# AccessBadgeV1_0.net
KiCad netlist of a schematic drawn in EAGLE
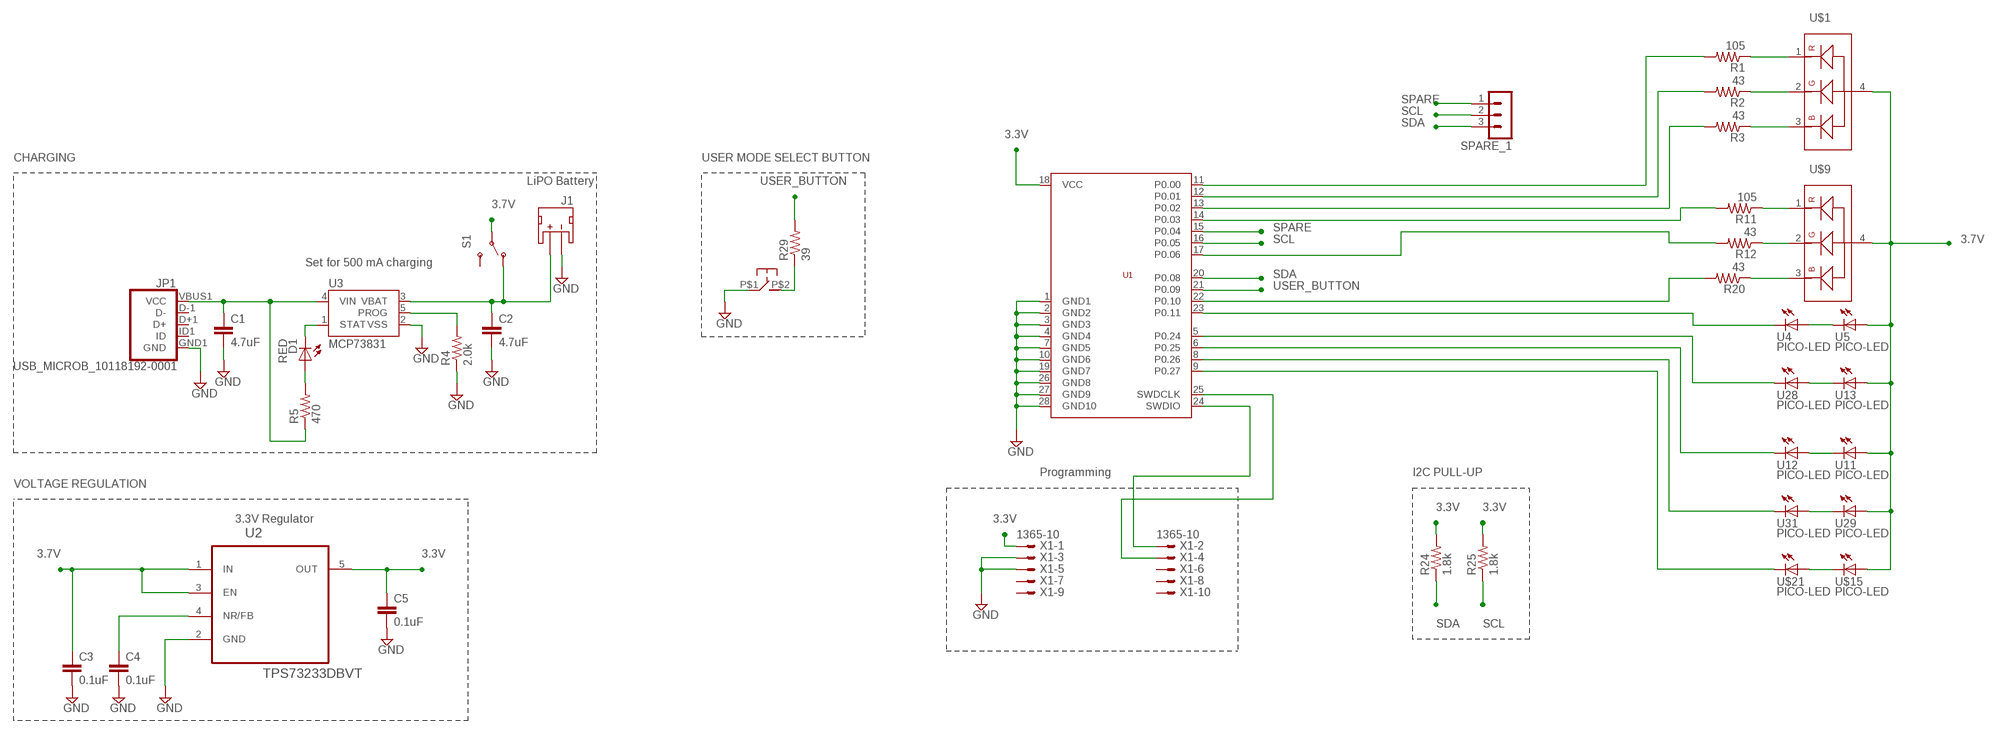
[diagram p0: schematic, sheet 1]

(export (version "E")
  (design (tool "Eeschema 10.0.6"))
  (components
    (comp (ref "C1")
      (value "4.7uF")
      (footprint "eagle-import:0603-CAP")
      (libsource (lib "eagle-import") (part "CAP0603-CAP"))
    )
    (comp (ref "C2")
      (value "4.7uF")
      (footprint "eagle-import:0603-CAP")
      (libsource (lib "eagle-import") (part "CAP0603-CAP"))
    )
    (comp (ref "C3")
      (value "0.1uF")
      (footprint "eagle-import:C0201")
      (libsource (lib "eagle-import") (part "C-EUC0201"))
    )
    (comp (ref "C4")
      (value "0.1uF")
      (footprint "eagle-import:C0201")
      (libsource (lib "eagle-import") (part "C-EUC0201"))
    )
    (comp (ref "C5")
      (value "0.1uF")
      (footprint "eagle-import:C0201")
      (libsource (lib "eagle-import") (part "C-EUC0201"))
    )
    (comp (ref "D1")
      (value "RED")
      (footprint "eagle-import:CHIP-LED0603")
      (libsource (lib "eagle-import") (part "LEDCHIP-LED0603"))
    )
    (comp (ref "J1")
      (value "JST_2MM_MALE")
      (footprint "eagle-import:JST-2-SMD")
      (libsource (lib "eagle-import") (part "JST_2MM_MALE"))
    )
    (comp (ref "JP1")
      (value "USB_MICROB_10118192-0001")
      (footprint "eagle-import:USB-B-MICRO-SMD_V03")
      (libsource (lib "eagle-import") (part "USB_MICROB_PLUGCONN-11752"))
    )
    (comp (ref "R1")
      (value "105")
      (footprint "eagle-import:R0201")
      (libsource (lib "eagle-import") (part "R-US_R0201"))
    )
    (comp (ref "R2")
      (value "43")
      (footprint "eagle-import:R0201")
      (libsource (lib "eagle-import") (part "R-US_R0201"))
    )
    (comp (ref "R3")
      (value "43")
      (footprint "eagle-import:R0201")
      (libsource (lib "eagle-import") (part "R-US_R0201"))
    )
    (comp (ref "R4")
      (value "2.0k")
      (footprint "eagle-import:R0201")
      (libsource (lib "eagle-import") (part "R-US_R0201"))
    )
    (comp (ref "R5")
      (value "470")
      (footprint "eagle-import:R0201")
      (libsource (lib "eagle-import") (part "R-US_R0201"))
    )
    (comp (ref "R11")
      (value "105")
      (footprint "eagle-import:R0201")
      (libsource (lib "eagle-import") (part "R-US_R0201"))
    )
    (comp (ref "R12")
      (value "43")
      (footprint "eagle-import:R0201")
      (libsource (lib "eagle-import") (part "R-US_R0201"))
    )
    (comp (ref "R20")
      (value "43")
      (footprint "eagle-import:R0201")
      (libsource (lib "eagle-import") (part "R-US_R0201"))
    )
    (comp (ref "R24")
      (value "1.8k")
      (footprint "eagle-import:R0201")
      (libsource (lib "eagle-import") (part "R-US_R0201"))
    )
    (comp (ref "R25")
      (value "1.8k")
      (footprint "eagle-import:R0201")
      (libsource (lib "eagle-import") (part "R-US_R0201"))
    )
    (comp (ref "R29")
      (value "39")
      (footprint "eagle-import:R0201")
      (libsource (lib "eagle-import") (part "R-US_R0201"))
    )
    (comp (ref "S1")
      (value "SWITCH-SPDTSMD2")
      (footprint "eagle-import:SWITCH-SPDT-SMD")
      (libsource (lib "eagle-import") (part "SWITCH-SPDTSMD2"))
    )
    (comp (ref "SLC")
      (value "TACTILE_BUTTON")
      (footprint "eagle-import:KXT131")
      (libsource (lib "eagle-import") (part "TACTILE_BUTTON"))
    )
    (comp (ref "SPARE_1")
      (value "MA03-1")
      (footprint "eagle-import:MA03-1")
      (libsource (lib "eagle-import") (part "MA03-1"))
    )
    (comp (ref "U$1")
      (value "RGB")
      (footprint "eagle-import:0606")
      (libsource (lib "eagle-import") (part "RGB"))
    )
    (comp (ref "U$9")
      (value "RGB")
      (footprint "eagle-import:0606")
      (libsource (lib "eagle-import") (part "RGB"))
    )
    (comp (ref "U$15")
      (value "PICO-LED")
      (footprint "eagle-import:CHIP-LED0402")
      (libsource (lib "eagle-import") (part "PICO-LED"))
    )
    (comp (ref "U$21")
      (value "PICO-LED")
      (footprint "eagle-import:CHIP-LED0402")
      (libsource (lib "eagle-import") (part "PICO-LED"))
    )
    (comp (ref "U1")
      (value "BMD-200")
      (footprint "eagle-import:BMD-200")
      (libsource (lib "eagle-import") (part "BMD-200"))
    )
    (comp (ref "U2")
      (value "TPS73233DBVT")
      (footprint "eagle-import:SOT95P280X145-5N")
      (libsource (lib "eagle-import") (part "TPS73233DBVT"))
    )
    (comp (ref "U3")
      (value "MCP73831")
      (footprint "eagle-import:SOT23-5")
      (libsource (lib "eagle-import") (part "MCP73831"))
    )
    (comp (ref "U4")
      (value "PICO-LED")
      (footprint "eagle-import:CHIP-LED0402")
      (libsource (lib "eagle-import") (part "PICO-LED"))
    )
    (comp (ref "U5")
      (value "PICO-LED")
      (footprint "eagle-import:CHIP-LED0402")
      (libsource (lib "eagle-import") (part "PICO-LED"))
    )
    (comp (ref "U11")
      (value "PICO-LED")
      (footprint "eagle-import:CHIP-LED0402")
      (libsource (lib "eagle-import") (part "PICO-LED"))
    )
    (comp (ref "U12")
      (value "PICO-LED")
      (footprint "eagle-import:CHIP-LED0402")
      (libsource (lib "eagle-import") (part "PICO-LED"))
    )
    (comp (ref "U13")
      (value "PICO-LED")
      (footprint "eagle-import:CHIP-LED0402")
      (libsource (lib "eagle-import") (part "PICO-LED"))
    )
    (comp (ref "U28")
      (value "PICO-LED")
      (footprint "eagle-import:CHIP-LED0402")
      (libsource (lib "eagle-import") (part "PICO-LED"))
    )
    (comp (ref "U29")
      (value "PICO-LED")
      (footprint "eagle-import:CHIP-LED0402")
      (libsource (lib "eagle-import") (part "PICO-LED"))
    )
    (comp (ref "U31")
      (value "PICO-LED")
      (footprint "eagle-import:CHIP-LED0402")
      (libsource (lib "eagle-import") (part "PICO-LED"))
    )
    (comp (ref "X1")
      (value "1365-10")
      (footprint "eagle-import:1365-10")
      (libsource (lib "eagle-import") (part "1365-10"))
    )
  )
  (nets
    (net (code "1") (name "/3.3V") (class "Default")
      (node (ref "C5") (pin "1") (pinfunction "1_1") (pintype "passive"))
      (node (ref "R24") (pin "2") (pinfunction "2_2") (pintype "passive"))
      (node (ref "R25") (pin "2") (pinfunction "2_2") (pintype "passive"))
      (node (ref "U1") (pin "18") (pinfunction "VCC_18") (pintype "bidirectional"))
      (node (ref "U2") (pin "5") (pinfunction "OUT_5") (pintype "output"))
      (node (ref "X1") (pin "1") (pinfunction "S_1") (pintype "passive"))
    )
    (net (code "2") (name "/3.7V") (class "Default")
      (node (ref "C3") (pin "1") (pinfunction "1_1") (pintype "passive"))
      (node (ref "S1") (pin "2") (pinfunction "P_2") (pintype "passive"))
      (node (ref "U$1") (pin "4") (pinfunction "4_4") (pintype "bidirectional"))
      (node (ref "U$15") (pin "P$1") (pinfunction "A_P$1") (pintype "passive"))
      (node (ref "U$9") (pin "4") (pinfunction "4_4") (pintype "bidirectional"))
      (node (ref "U11") (pin "P$1") (pinfunction "A_P$1") (pintype "passive"))
      (node (ref "U13") (pin "P$1") (pinfunction "A_P$1") (pintype "passive"))
      (node (ref "U2") (pin "1") (pinfunction "IN_1") (pintype "power_in"))
      (node (ref "U2") (pin "3") (pinfunction "EN_3") (pintype "input"))
      (node (ref "U29") (pin "P$1") (pinfunction "A_P$1") (pintype "passive"))
      (node (ref "U5") (pin "P$1") (pinfunction "A_P$1") (pintype "passive"))
    )
    (net (code "3") (name "/SCL") (class "Default")
      (node (ref "R25") (pin "1") (pinfunction "1_1") (pintype "passive"))
      (node (ref "SPARE_1") (pin "2") (pinfunction "2_2") (pintype "passive"))
      (node (ref "U1") (pin "16") (pinfunction "P0.05_16") (pintype "bidirectional"))
    )
    (net (code "4") (name "/SDA") (class "Default")
      (node (ref "R24") (pin "1") (pinfunction "1_1") (pintype "passive"))
      (node (ref "SPARE_1") (pin "3") (pinfunction "3_3") (pintype "passive"))
      (node (ref "U1") (pin "20") (pinfunction "P0.08_20") (pintype "bidirectional"))
    )
    (net (code "5") (name "/SPARE") (class "Default")
      (node (ref "SPARE_1") (pin "1") (pinfunction "1_1") (pintype "passive"))
      (node (ref "U1") (pin "15") (pinfunction "P0.04_15") (pintype "bidirectional"))
    )
    (net (code "6") (name "/USER_BUTTON") (class "Default")
      (node (ref "R29") (pin "2") (pinfunction "2_2") (pintype "passive"))
      (node (ref "U1") (pin "21") (pinfunction "P0.09_21") (pintype "bidirectional"))
    )
    (net (code "7") (name "GND") (class "Default")
      (node (ref "C1") (pin "2") (pinfunction "2_2") (pintype "passive"))
      (node (ref "C2") (pin "2") (pinfunction "2_2") (pintype "passive"))
      (node (ref "C3") (pin "2") (pinfunction "2_2") (pintype "passive"))
      (node (ref "C4") (pin "2") (pinfunction "2_2") (pintype "passive"))
      (node (ref "C5") (pin "2") (pinfunction "2_2") (pintype "passive"))
      (node (ref "J1") (pin "1") (pinfunction "-_1") (pintype "bidirectional"))
      (node (ref "JP1") (pin "GND1") (pinfunction "GND_GND1") (pintype "bidirectional"))
      (node (ref "R4") (pin "1") (pinfunction "1_1") (pintype "passive"))
      (node (ref "SLC") (pin "P$1") (pinfunction "P$1_P$1") (pintype "bidirectional"))
      (node (ref "U1") (pin "1") (pinfunction "GND1_1") (pintype "bidirectional"))
      (node (ref "U1") (pin "10") (pinfunction "GND6_10") (pintype "bidirectional"))
      (node (ref "U1") (pin "19") (pinfunction "GND7_19") (pintype "bidirectional"))
      (node (ref "U1") (pin "2") (pinfunction "GND2_2") (pintype "bidirectional"))
      (node (ref "U1") (pin "26") (pinfunction "GND8_26") (pintype "bidirectional"))
      (node (ref "U1") (pin "27") (pinfunction "GND9_27") (pintype "bidirectional"))
      (node (ref "U1") (pin "28") (pinfunction "GND10_28") (pintype "bidirectional"))
      (node (ref "U1") (pin "3") (pinfunction "GND3_3") (pintype "bidirectional"))
      (node (ref "U1") (pin "4") (pinfunction "GND4_4") (pintype "bidirectional"))
      (node (ref "U1") (pin "7") (pinfunction "GND5_7") (pintype "bidirectional"))
      (node (ref "U2") (pin "2") (pinfunction "GND_2") (pintype "passive"))
      (node (ref "U3") (pin "2") (pinfunction "VSS_2") (pintype "power_in"))
      (node (ref "X1") (pin "3") (pinfunction "S_3") (pintype "passive"))
      (node (ref "X1") (pin "5") (pinfunction "S_5") (pintype "passive"))
    )
    (net (code "8") (name "Net-(D1-PadA)") (class "Default")
      (node (ref "D1") (pin "A") (pinfunction "A_A") (pintype "passive"))
      (node (ref "R5") (pin "2") (pinfunction "2_2") (pintype "passive"))
    )
    (net (code "9") (name "Net-(J1-+)") (class "Default")
      (node (ref "C2") (pin "1") (pinfunction "1_1") (pintype "passive"))
      (node (ref "J1") (pin "2") (pinfunction "+_2") (pintype "bidirectional"))
      (node (ref "S1") (pin "1") (pinfunction "O_1") (pintype "passive"))
      (node (ref "U3") (pin "3") (pinfunction "VBAT_3") (pintype "power_in"))
    )
    (net (code "10") (name "Net-(JP1-VCC)") (class "Default")
      (node (ref "C1") (pin "1") (pinfunction "1_1") (pintype "passive"))
      (node (ref "JP1") (pin "VBUS1") (pinfunction "VCC_VBUS1") (pintype "bidirectional"))
      (node (ref "R5") (pin "1") (pinfunction "1_1") (pintype "passive"))
      (node (ref "U3") (pin "4") (pinfunction "VIN_4") (pintype "power_in"))
    )
    (net (code "11") (name "Net-(R1-Pad1)") (class "Default")
      (node (ref "R1") (pin "1") (pinfunction "1_1") (pintype "passive"))
      (node (ref "U$1") (pin "1") (pinfunction "1_1") (pintype "bidirectional"))
    )
    (net (code "12") (name "Net-(R2-Pad1)") (class "Default")
      (node (ref "R2") (pin "1") (pinfunction "1_1") (pintype "passive"))
      (node (ref "U$1") (pin "2") (pinfunction "2_2") (pintype "bidirectional"))
    )
    (net (code "13") (name "Net-(R3-Pad1)") (class "Default")
      (node (ref "R3") (pin "1") (pinfunction "1_1") (pintype "passive"))
      (node (ref "U$1") (pin "3") (pinfunction "3_3") (pintype "bidirectional"))
    )
    (net (code "14") (name "Net-(R11-Pad1)") (class "Default")
      (node (ref "R11") (pin "1") (pinfunction "1_1") (pintype "passive"))
      (node (ref "U$9") (pin "1") (pinfunction "1_1") (pintype "bidirectional"))
    )
    (net (code "15") (name "Net-(R12-Pad1)") (class "Default")
      (node (ref "R12") (pin "1") (pinfunction "1_1") (pintype "passive"))
      (node (ref "U$9") (pin "2") (pinfunction "2_2") (pintype "bidirectional"))
    )
    (net (code "16") (name "Net-(R20-Pad1)") (class "Default")
      (node (ref "R20") (pin "1") (pinfunction "1_1") (pintype "passive"))
      (node (ref "U$9") (pin "3") (pinfunction "3_3") (pintype "bidirectional"))
    )
    (net (code "17") (name "Net-(R29-Pad1)") (class "Default")
      (node (ref "R29") (pin "1") (pinfunction "1_1") (pintype "passive"))
      (node (ref "SLC") (pin "P$2") (pinfunction "P$2_P$2") (pintype "bidirectional"))
    )
    (net (code "18") (name "Net-(U$15-C)") (class "Default")
      (node (ref "U$15") (pin "P$2") (pinfunction "C_P$2") (pintype "passive"))
      (node (ref "U$21") (pin "P$1") (pinfunction "A_P$1") (pintype "passive"))
    )
    (net (code "19") (name "Net-(U$21-C)") (class "Default")
      (node (ref "U$21") (pin "P$2") (pinfunction "C_P$2") (pintype "passive"))
      (node (ref "U1") (pin "9") (pinfunction "P0.27_9") (pintype "bidirectional"))
    )
    (net (code "20") (name "Net-(U1-P0.00)") (class "Default")
      (node (ref "R1") (pin "2") (pinfunction "2_2") (pintype "passive"))
      (node (ref "U1") (pin "11") (pinfunction "P0.00_11") (pintype "bidirectional"))
    )
    (net (code "21") (name "Net-(U1-P0.01)") (class "Default")
      (node (ref "R2") (pin "2") (pinfunction "2_2") (pintype "passive"))
      (node (ref "U1") (pin "12") (pinfunction "P0.01_12") (pintype "bidirectional"))
    )
    (net (code "22") (name "Net-(U1-P0.02)") (class "Default")
      (node (ref "R3") (pin "2") (pinfunction "2_2") (pintype "passive"))
      (node (ref "U1") (pin "13") (pinfunction "P0.02_13") (pintype "bidirectional"))
    )
    (net (code "23") (name "Net-(U1-P0.03)") (class "Default")
      (node (ref "R11") (pin "2") (pinfunction "2_2") (pintype "passive"))
      (node (ref "U1") (pin "14") (pinfunction "P0.03_14") (pintype "bidirectional"))
    )
    (net (code "24") (name "Net-(U1-P0.06)") (class "Default")
      (node (ref "R12") (pin "2") (pinfunction "2_2") (pintype "passive"))
      (node (ref "U1") (pin "17") (pinfunction "P0.06_17") (pintype "bidirectional"))
    )
    (net (code "25") (name "Net-(U1-P0.10)") (class "Default")
      (node (ref "R20") (pin "2") (pinfunction "2_2") (pintype "passive"))
      (node (ref "U1") (pin "22") (pinfunction "P0.10_22") (pintype "bidirectional"))
    )
    (net (code "26") (name "Net-(U1-P0.11)") (class "Default")
      (node (ref "U1") (pin "23") (pinfunction "P0.11_23") (pintype "bidirectional"))
      (node (ref "U4") (pin "P$2") (pinfunction "C_P$2") (pintype "passive"))
    )
    (net (code "27") (name "Net-(U1-P0.24)") (class "Default")
      (node (ref "U1") (pin "5") (pinfunction "P0.24_5") (pintype "bidirectional"))
      (node (ref "U28") (pin "P$2") (pinfunction "C_P$2") (pintype "passive"))
    )
    (net (code "28") (name "Net-(U1-P0.25)") (class "Default")
      (node (ref "U1") (pin "6") (pinfunction "P0.25_6") (pintype "bidirectional"))
      (node (ref "U12") (pin "P$2") (pinfunction "C_P$2") (pintype "passive"))
    )
    (net (code "29") (name "Net-(U1-P0.26)") (class "Default")
      (node (ref "U1") (pin "8") (pinfunction "P0.26_8") (pintype "bidirectional"))
      (node (ref "U31") (pin "P$2") (pinfunction "C_P$2") (pintype "passive"))
    )
    (net (code "30") (name "Net-(U1-SWDCLK)") (class "Default")
      (node (ref "U1") (pin "25") (pinfunction "SWDCLK_25") (pintype "bidirectional"))
      (node (ref "X1") (pin "4") (pinfunction "S_4") (pintype "passive"))
    )
    (net (code "31") (name "Net-(U1-SWDIO)") (class "Default")
      (node (ref "U1") (pin "24") (pinfunction "SWDIO_24") (pintype "bidirectional"))
      (node (ref "X1") (pin "2") (pinfunction "S_2") (pintype "passive"))
    )
    (net (code "32") (name "Net-(U2-NR{slash}FB)") (class "Default")
      (node (ref "C4") (pin "1") (pinfunction "1_1") (pintype "passive"))
      (node (ref "U2") (pin "4") (pinfunction "NR/FB_4") (pintype "input"))
    )
    (net (code "33") (name "Net-(U3-PROG)") (class "Default")
      (node (ref "R4") (pin "2") (pinfunction "2_2") (pintype "passive"))
      (node (ref "U3") (pin "5") (pinfunction "PROG_5") (pintype "input"))
    )
    (net (code "34") (name "Net-(U3-STAT)") (class "Default")
      (node (ref "D1") (pin "C") (pinfunction "C_C") (pintype "passive"))
      (node (ref "U3") (pin "1") (pinfunction "STAT_1") (pintype "output"))
    )
    (net (code "35") (name "Net-(U4-A)") (class "Default")
      (node (ref "U4") (pin "P$1") (pinfunction "A_P$1") (pintype "passive"))
      (node (ref "U5") (pin "P$2") (pinfunction "C_P$2") (pintype "passive"))
    )
    (net (code "36") (name "Net-(U11-C)") (class "Default")
      (node (ref "U11") (pin "P$2") (pinfunction "C_P$2") (pintype "passive"))
      (node (ref "U12") (pin "P$1") (pinfunction "A_P$1") (pintype "passive"))
    )
    (net (code "37") (name "Net-(U13-C)") (class "Default")
      (node (ref "U13") (pin "P$2") (pinfunction "C_P$2") (pintype "passive"))
      (node (ref "U28") (pin "P$1") (pinfunction "A_P$1") (pintype "passive"))
    )
    (net (code "38") (name "Net-(U29-C)") (class "Default")
      (node (ref "U29") (pin "P$2") (pinfunction "C_P$2") (pintype "passive"))
      (node (ref "U31") (pin "P$1") (pinfunction "A_P$1") (pintype "passive"))
    )
    (net (code "39") (name "unconnected-(J1-PAD1-PadNC1)") (class "Default")
      (node (ref "J1") (pin "NC1") (pinfunction "PAD1_NC1") (pintype "bidirectional"))
    )
    (net (code "40") (name "unconnected-(J1-PAD2-PadNC2)") (class "Default")
      (node (ref "J1") (pin "NC2") (pinfunction "PAD2_NC2") (pintype "bidirectional"))
    )
    (net (code "41") (name "unconnected-(JP1-D+-PadD+1)") (class "Default")
      (node (ref "JP1") (pin "D+1") (pinfunction "D+_D+1") (pintype "bidirectional"))
    )
    (net (code "42") (name "unconnected-(JP1-D--PadD-1)") (class "Default")
      (node (ref "JP1") (pin "D-1") (pinfunction "D-_D-1") (pintype "bidirectional"))
    )
    (net (code "43") (name "unconnected-(JP1-ID-PadID1)") (class "Default")
      (node (ref "JP1") (pin "ID1") (pinfunction "ID_ID1") (pintype "bidirectional"))
    )
    (net (code "44") (name "unconnected-(S1-S-Pad3)") (class "Default")
      (node (ref "S1") (pin "3") (pinfunction "S_3") (pintype "passive"))
    )
    (net (code "45") (name "unconnected-(X1B-S-Pad10)") (class "Default")
      (node (ref "X1") (pin "10") (pinfunction "S_10") (pintype "passive"))
    )
    (net (code "46") (name "unconnected-(X1G-S-Pad6)") (class "Default")
      (node (ref "X1") (pin "6") (pinfunction "S_6") (pintype "passive"))
    )
    (net (code "47") (name "unconnected-(X1H-S-Pad7)") (class "Default")
      (node (ref "X1") (pin "7") (pinfunction "S_7") (pintype "passive"))
    )
    (net (code "48") (name "unconnected-(X1I-S-Pad8)") (class "Default")
      (node (ref "X1") (pin "8") (pinfunction "S_8") (pintype "passive"))
    )
    (net (code "49") (name "unconnected-(X1J-S-Pad9)") (class "Default")
      (node (ref "X1") (pin "9") (pinfunction "S_9") (pintype "passive"))
    )
  )
)
